# Micro.net
KiCad netlist of a schematic drawn in Altium Designer
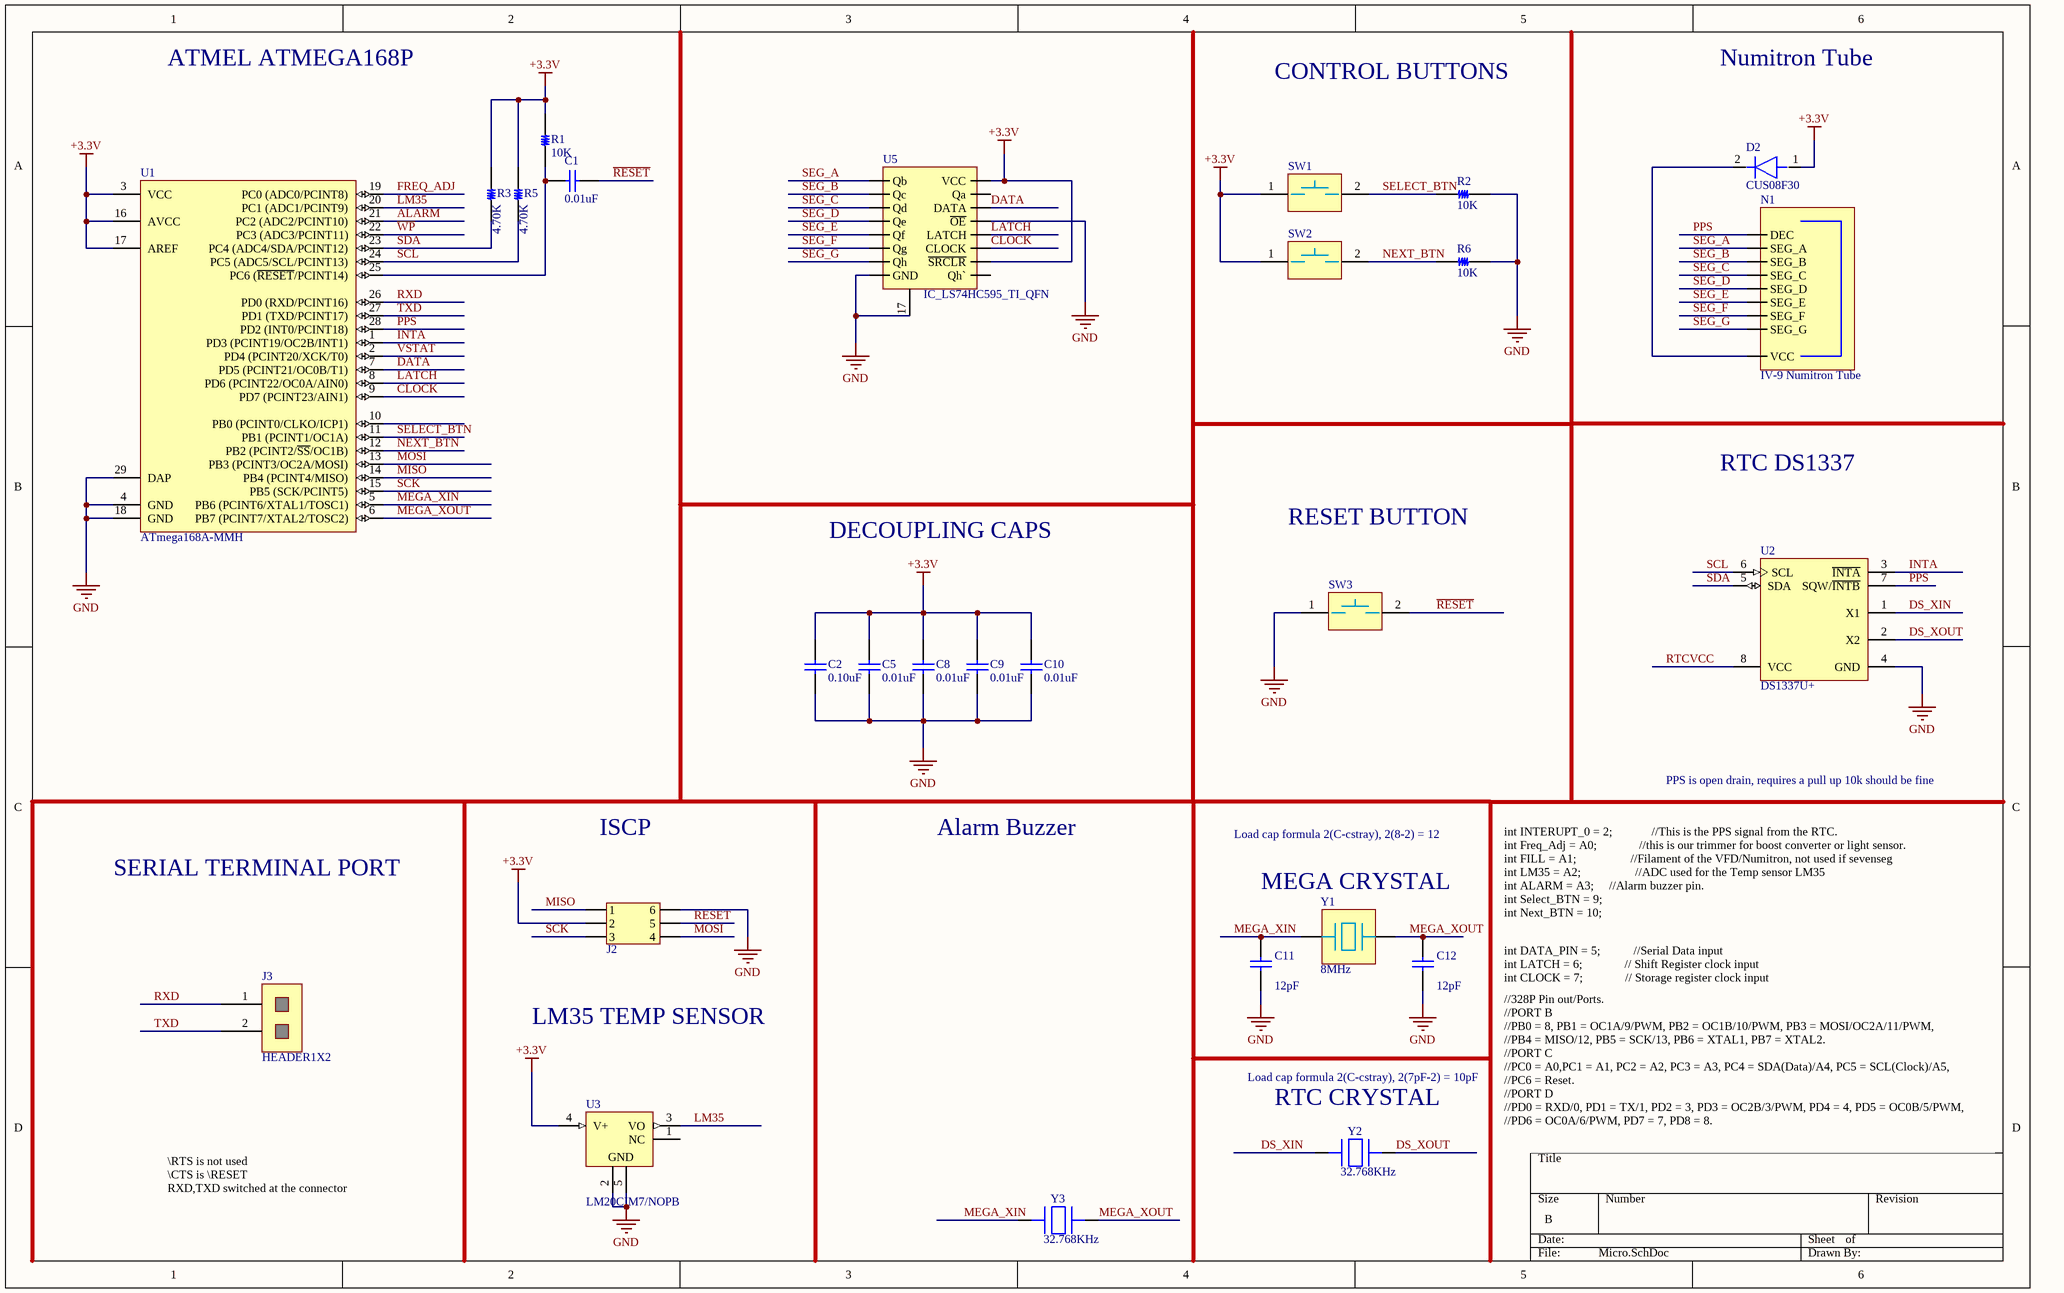
[diagram p0: Micro.SchDoc]

(export (version "E")
  (design (tool "Eeschema 10.0.6"))
  (components
    (comp (ref "C1")
      (value "0.01uF")
      (footprint "DISCRETE:C1608N")
      (description "CAP CER 10000PF 50V 5% X7R 0603")
      (fields (field (name "TOLERANCE") "10%") (field (name "VOLTAGE") "50V"))
      (libsource (lib "DISCRETE_CAP") (part "C103_0603_X7R_50V0_5%_Kemet"))
    )
    (comp (ref "C2")
      (value "0.10uF")
      (footprint "DISCRETE:C1005N")
      (description "CAP CER 0.1UF 16V 10% X7R 0402")
      (fields (field (name "Comment") "C104_0402_X7R_16V0_10%_Kemet"))
      (libsource (lib "DISCRETE_CAP") (part "C104_0402_X7R_16V0_10%_Kemet"))
    )
    (comp (ref "C5")
      (value "0.01uF")
      (footprint "DISCRETE:C1005N")
      (description "CAP CER 10000PF 25V 5% X7R 0402")
      (fields (field (name "TOLERANCE") "5%") (field (name "VOLTAGE") "25V"))
      (libsource (lib "DISCRETE_CAP") (part "C103_0402_X7R_25.0V_5%_Kemet"))
    )
    (comp (ref "C8")
      (value "0.01uF")
      (footprint "DISCRETE:C1005N")
      (description "CAP CER 10000PF 25V 5% X7R 0402")
      (fields (field (name "TOLERANCE") "5%") (field (name "VOLTAGE") "25V"))
      (libsource (lib "DISCRETE_CAP") (part "C103_0402_X7R_25.0V_5%_Kemet"))
    )
    (comp (ref "C9")
      (value "0.01uF")
      (footprint "DISCRETE:C1005N")
      (description "CAP CER 10000PF 25V 5% X7R 0402")
      (fields (field (name "TOLERANCE") "5%") (field (name "VOLTAGE") "25V"))
      (libsource (lib "DISCRETE_CAP") (part "C103_0402_X7R_25.0V_5%_Kemet"))
    )
    (comp (ref "C10")
      (value "0.01uF")
      (footprint "DISCRETE:C1005N")
      (description "CAP CER 10000PF 25V 5% X7R 0402")
      (fields (field (name "TOLERANCE") "5%") (field (name "VOLTAGE") "25V"))
      (libsource (lib "DISCRETE_CAP") (part "C103_0402_X7R_25.0V_5%_Kemet"))
    )
    (comp (ref "C11")
      (value "12pF")
      (footprint "DISCRETE:C1608L")
      (description "CAP CER 12PF 50V 5% C0G 0603")
      (fields (field (name "Comment") "C120-0603-COG-NPO-5%"))
      (libsource (lib "DISCRETE_CAP") (part "C120-0603-C0G-NPO-5%_TDK"))
    )
    (comp (ref "C12")
      (value "12pF")
      (footprint "DISCRETE:C1608L")
      (description "CAP CER 12PF 50V 5% C0G 0603")
      (fields (field (name "Comment") "C120-0603-COG-NPO-5%"))
      (libsource (lib "DISCRETE_CAP") (part "C120-0603-C0G-NPO-5%_TDK"))
    )
    (comp (ref "D2")
      (value "CUS08F30")
      (footprint "DISCRETE:DIODE-USC")
      (description "DIODE SCHOTTKY 30V 800MA USC")
      (libsource (lib "DISCRETE_DIODE") (part "DIODE-CUS08F30-30v-800MA-USC-Toshiba"))
    )
    (comp (ref "J2")
      (value "HEADER 3x2 50mil FCI")
      (footprint "EMACH_CON:3x2 50mil header_FCI")
      (description "CONN HEADER 6POS DL UNSHRD SMD")
      (libsource (lib "EMACH_CON") (part "HEADER 3x2 50mil FCI"))
    )
    (comp (ref "J3")
      (value "HEADER1X2")
      (footprint "EMECH_CONNECTOR:CONN_2P_SINGLE_100MIL")
      (fields (field (name "MANUFACTURER") "MOLEX") (field (name "PART NUMBER") "22-28-4360"))
      (libsource (lib "EMECH_CONNECTOR") (part "CONN_2P_Header"))
    )
    (comp (ref "N1")
      (value "IV-9 Numitron Tube")
      (footprint "TPH:IV-9 Straight Header")
      (libsource (lib "TPH") (part "IV-9 Numitron Tube"))
    )
    (comp (ref "R1")
      (value "10K")
      (footprint "DISCRETE:C1005N")
      (description "RES 10K OHM 1/10W 5% 0402 SMD")
      (fields (field (name "TOLERANCE") "5%"))
      (libsource (lib "DISCRETE_RESISTOR") (part "R103_0402_5%_Panasonic"))
    )
    (comp (ref "R2")
      (value "10K")
      (footprint "DISCRETE:C1005N")
      (description "RES 10K OHM 1/10W 5% 0402 SMD")
      (fields (field (name "TOLERANCE") "5%"))
      (libsource (lib "DISCRETE_RESISTOR") (part "R103_0402_5%_Panasonic"))
    )
    (comp (ref "R3")
      (value "4.70K")
      (footprint "DISCRETE:C1005N")
      (description "RES 4.7K OHM 1/10W 1% 0402 SMD")
      (fields (field (name "TOLERANCE") "1%") (field (name "Comment") "R472-0402-1%"))
      (libsource (lib "DISCRETE_RESISTOR") (part "R472-0402-1%"))
    )
    (comp (ref "R5")
      (value "4.70K")
      (footprint "DISCRETE:C1005N")
      (description "RES 4.7K OHM 1/10W 1% 0402 SMD")
      (fields (field (name "TOLERANCE") "1%") (field (name "Comment") "R472-0402-1%"))
      (libsource (lib "DISCRETE_RESISTOR") (part "R472-0402-1%"))
    )
    (comp (ref "R6")
      (value "10K")
      (footprint "DISCRETE:C1005N")
      (description "RES 10K OHM 1/10W 5% 0402 SMD")
      (fields (field (name "TOLERANCE") "5%"))
      (libsource (lib "DISCRETE_RESISTOR") (part "R103_0402_5%_Panasonic"))
    )
    (comp (ref "SW1")
      (value "SPST-NO_6mm_x_3.5mm")
      (footprint "SWITCH:SPST_NO_6x3.5")
      (description "SWITCH TACTILE SPST-NO 0.05A 24V")
      (libsource (lib "SWITCH") (part "SPST-NO_6mm_x_3.5mm"))
    )
    (comp (ref "SW2")
      (value "SPST-NO_6mm_x_3.5mm")
      (footprint "SWITCH:SPST_NO_6x3.5")
      (description "SWITCH TACTILE SPST-NO 0.05A 24V")
      (libsource (lib "SWITCH") (part "SPST-NO_6mm_x_3.5mm"))
    )
    (comp (ref "SW3")
      (value "SPST-NO_6mm_x_3.5mm")
      (footprint "SWITCH:SPST_NO_6x3.5")
      (description "SWITCH TACTILE SPST-NO 0.05A 24V")
      (libsource (lib "SWITCH") (part "SPST-NO_6mm_x_3.5mm"))
    )
    (comp (ref "U1")
      (value "ATmega168A-MMH")
      (footprint "28M1_N")
      (libsource (lib "Microcontroller megaAVR") (part "ATmega168A-MMH"))
    )
    (comp (ref "U2")
      (value "DS1337U+")
      (footprint "U8+1_N")
      (description "I2C Serial Real-Time Clock, 8-Pin uSOP, -40 to 85 degC, Pb-Free")
      (libsource (lib "Real-Time Clocks (RTCs)") (part "DS1337U+"))
    )
    (comp (ref "U3")
      (value "LM20CIM7/NOPB")
      (footprint "MAA05A_N")
      (description "2.4V, 10µA Temperature Sensor, 5-pin SC-70 Micro SMD, Pb-Free")
      (fields (field (name "MANUFACTURER") "National Semiconductor"))
      (libsource (lib "Temperature Sensor") (part "LM20CIM7/NOPB"))
    )
    (comp (ref "U5")
      (value "IC_LS74HC595_TI_QFN")
      (footprint "IC:QFN50P350X250X100_HS-17N")
      (description "IC 8-BIT SHIFT REGISTER 16-DIP")
      (libsource (lib "TPH") (part "IC_LS74HC595_TI_QFN"))
    )
    (comp (ref "Y1")
      (value "8MHz")
      (footprint "IC:NDK_8MHZ_CRYSTAL")
      (description "Crystal 8.0000MHz 50ppm 8pF 500 Ohm -40°C - 150°C AEC-Q200 Surface Mount 2-SMD")
      (fields (field (name "Comment") "CRYSTAL_8Mhz_8pF_Micro_NDK"))
      (libsource (lib "Crystal") (part "CRYSTAL_8Mhz_8pF_Micro_NDK"))
    )
    (comp (ref "Y2")
      (value "32.768KHz")
      (footprint "EMECH_PIEZO:ABS05")
      (description "Crystal 32.7680kHz 20ppm 12.5pF 90 kOhm -40°C - 85°C Surface Mount 2-SMD")
      (libsource (lib "EMECH_PIEZO") (part "CRYSTAL-32.768KHZ_ABS-Micro"))
    )
    (comp (ref "Y3")
      (value "32.768KHz")
      (footprint "EMECH_PIEZO:ABS05")
      (description "Crystal 32.7680kHz 20ppm 12.5pF 90 kOhm -40°C - 85°C Surface Mount 2-SMD")
      (libsource (lib "EMECH_PIEZO") (part "CRYSTAL-32.768KHZ_ABS-Micro"))
    )
  )
  (nets
    (net (code "1") (name "+3.3V") (class "Default")
      (node (ref "C10") (pin "2") (pinfunction "2_2") (pintype "passive"))
      (node (ref "C2") (pin "2") (pinfunction "2_2") (pintype "passive"))
      (node (ref "C5") (pin "2") (pinfunction "2_2") (pintype "passive"))
      (node (ref "C8") (pin "2") (pinfunction "2_2") (pintype "passive"))
      (node (ref "C9") (pin "2") (pinfunction "2_2") (pintype "passive"))
      (node (ref "D2") (pin "1") (pintype "passive"))
      (node (ref "J2") (pin "2") (pinfunction "2_2") (pintype "passive"))
      (node (ref "R1") (pin "2") (pinfunction "2_2") (pintype "passive"))
      (node (ref "R3") (pin "2") (pinfunction "2_2") (pintype "passive"))
      (node (ref "R5") (pin "2") (pinfunction "2_2") (pintype "passive"))
      (node (ref "SW1") (pin "1") (pinfunction "1_1") (pintype "passive"))
      (node (ref "SW2") (pin "1") (pinfunction "1_1") (pintype "passive"))
      (node (ref "U1") (pin "16") (pinfunction "AVCC_16") (pintype "power_in"))
      (node (ref "U1") (pin "17") (pinfunction "AREF_17") (pintype "power_in"))
      (node (ref "U1") (pin "3") (pinfunction "VCC_3") (pintype "power_in"))
      (node (ref "U3") (pin "4") (pinfunction "V+_4") (pintype "input"))
      (node (ref "U5") (pin "10") (pinfunction "SRCLR_10") (pintype "passive"))
      (node (ref "U5") (pin "16") (pinfunction "VCC_16") (pintype "passive"))
    )
    (net (code "2") (name "/ALARM") (class "Default")
      (node (ref "U1") (pin "21") (pinfunction "PC2_(ADC2/PCINT10)_21") (pintype "bidirectional"))
    )
    (net (code "3") (name "/CLOCK") (class "Default")
      (node (ref "U1") (pin "9") (pinfunction "PD7_(PCINT23/AIN1)_9") (pintype "bidirectional"))
      (node (ref "U5") (pin "11") (pinfunction "CLOCK_11") (pintype "passive"))
    )
    (net (code "4") (name "/DATA") (class "Default")
      (node (ref "U1") (pin "7") (pinfunction "PD5_(PCINT21/OC0B/T1)_7") (pintype "bidirectional"))
      (node (ref "U5") (pin "14") (pinfunction "DATA_14") (pintype "passive"))
    )
    (net (code "5") (name "/DS_XIN") (class "Default")
      (node (ref "U2") (pin "1") (pinfunction "X1_1") (pintype "passive"))
      (node (ref "Y2") (pin "2") (pintype "passive"))
    )
    (net (code "6") (name "/DS_XOUT") (class "Default")
      (node (ref "U2") (pin "2") (pinfunction "X2_2") (pintype "passive"))
      (node (ref "Y2") (pin "1") (pintype "passive"))
    )
    (net (code "7") (name "/FREQ_ADJ") (class "Default")
      (node (ref "U1") (pin "19") (pinfunction "PC0_(ADC0/PCINT8)_19") (pintype "bidirectional"))
    )
    (net (code "8") (name "/INTA") (class "Default")
      (node (ref "U1") (pin "1") (pinfunction "PD3_(PCINT19/OC2B/INT1)_1") (pintype "bidirectional"))
      (node (ref "U2") (pin "3") (pinfunction "~{INTA}_3") (pintype "open_collector"))
    )
    (net (code "9") (name "/LATCH") (class "Default")
      (node (ref "U1") (pin "8") (pinfunction "PD6_(PCINT22/OC0A/AIN0)_8") (pintype "bidirectional"))
      (node (ref "U5") (pin "12") (pinfunction "LATCH_12") (pintype "passive"))
    )
    (net (code "10") (name "/LM35") (class "Default")
      (node (ref "U1") (pin "20") (pinfunction "PC1_(ADC1/PCINT9)_20") (pintype "bidirectional"))
      (node (ref "U3") (pin "3") (pinfunction "VO_3") (pintype "output"))
    )
    (net (code "11") (name "/MEGA_XIN") (class "Default")
      (node (ref "C11") (pin "2") (pinfunction "2_2") (pintype "passive"))
      (node (ref "U1") (pin "5") (pinfunction "PB6_(PCINT6/XTAL1/TOSC1)_5") (pintype "bidirectional"))
      (node (ref "Y1") (pin "1") (pinfunction "1_1") (pintype "passive"))
      (node (ref "Y3") (pin "2") (pintype "passive"))
    )
    (net (code "12") (name "/MEGA_XOUT") (class "Default")
      (node (ref "C12") (pin "2") (pinfunction "2_2") (pintype "passive"))
      (node (ref "U1") (pin "6") (pinfunction "PB7_(PCINT7/XTAL2/TOSC2)_6") (pintype "bidirectional"))
      (node (ref "Y1") (pin "2") (pinfunction "2_2") (pintype "passive"))
      (node (ref "Y3") (pin "1") (pintype "passive"))
    )
    (net (code "13") (name "/MISO") (class "Default")
      (node (ref "J2") (pin "1") (pinfunction "1_1") (pintype "passive"))
      (node (ref "U1") (pin "14") (pinfunction "PB4_(PCINT4/MISO)_14") (pintype "bidirectional"))
    )
    (net (code "14") (name "/MOSI") (class "Default")
      (node (ref "J2") (pin "4") (pinfunction "4_4") (pintype "passive"))
      (node (ref "U1") (pin "13") (pinfunction "PB3_(PCINT3/OC2A/MOSI)_13") (pintype "bidirectional"))
    )
    (net (code "15") (name "/NEXT_BTN") (class "Default")
      (node (ref "R6") (pin "2") (pinfunction "2_2") (pintype "passive"))
      (node (ref "SW2") (pin "2") (pinfunction "2_2") (pintype "passive"))
      (node (ref "U1") (pin "12") (pinfunction "PB2_(PCINT2/~{SS}/OC1B)_12") (pintype "bidirectional"))
    )
    (net (code "16") (name "/PPS") (class "Default")
      (node (ref "N1") (pin "2") (pinfunction "DEC_2") (pintype "passive"))
      (node (ref "U1") (pin "28") (pinfunction "PD2_(INT0/PCINT18)_28") (pintype "bidirectional"))
      (node (ref "U2") (pin "7") (pinfunction "SQW/~{INTB}_7") (pintype "open_collector"))
    )
    (net (code "17") (name "/RESET") (class "Default")
      (node (ref "C1") (pin "1") (pinfunction "1_1") (pintype "passive"))
      (node (ref "J2") (pin "5") (pinfunction "5_5") (pintype "passive"))
      (node (ref "SW3") (pin "2") (pinfunction "2_2") (pintype "passive"))
    )
    (net (code "18") (name "/RTCVCC") (class "Default")
      (node (ref "U2") (pin "8") (pinfunction "VCC_8") (pintype "power_in"))
    )
    (net (code "19") (name "/RXD") (class "Default")
      (node (ref "J3") (pin "1") (pinfunction "1_1") (pintype "passive"))
      (node (ref "U1") (pin "26") (pinfunction "PD0_(RXD/PCINT16)_26") (pintype "bidirectional"))
    )
    (net (code "20") (name "/SCK") (class "Default")
      (node (ref "J2") (pin "3") (pinfunction "3_3") (pintype "passive"))
      (node (ref "U1") (pin "15") (pinfunction "PB5_(SCK/PCINT5)_15") (pintype "bidirectional"))
    )
    (net (code "21") (name "/SCL") (class "Default")
      (node (ref "R5") (pin "1") (pinfunction "1_1") (pintype "passive"))
      (node (ref "U1") (pin "24") (pinfunction "PC5_(ADC5/SCL/PCINT13)_24") (pintype "bidirectional"))
      (node (ref "U2") (pin "6") (pinfunction "SCL_6") (pintype "input"))
    )
    (net (code "22") (name "/SDA") (class "Default")
      (node (ref "R3") (pin "1") (pinfunction "1_1") (pintype "passive"))
      (node (ref "U1") (pin "23") (pinfunction "PC4_(ADC4/SDA/PCINT12)_23") (pintype "bidirectional"))
      (node (ref "U2") (pin "5") (pinfunction "SDA_5") (pintype "bidirectional"))
    )
    (net (code "23") (name "/SEG_A") (class "Default")
      (node (ref "N1") (pin "5") (pinfunction "SEG_A_5") (pintype "passive"))
      (node (ref "U5") (pin "1") (pinfunction "Qb_1") (pintype "passive"))
    )
    (net (code "24") (name "/SEG_B") (class "Default")
      (node (ref "N1") (pin "3") (pinfunction "SEG_B_3") (pintype "passive"))
      (node (ref "U5") (pin "2") (pinfunction "Qc_2") (pintype "passive"))
    )
    (net (code "25") (name "/SEG_C") (class "Default")
      (node (ref "N1") (pin "4") (pinfunction "SEG_C_4") (pintype "passive"))
      (node (ref "U5") (pin "3") (pinfunction "Qd_3") (pintype "passive"))
    )
    (net (code "26") (name "/SEG_D") (class "Default")
      (node (ref "N1") (pin "8") (pinfunction "SEG_D_8") (pintype "passive"))
      (node (ref "U5") (pin "4") (pinfunction "Qe_4") (pintype "passive"))
    )
    (net (code "27") (name "/SEG_E") (class "Default")
      (node (ref "N1") (pin "9") (pinfunction "SEG_E_9") (pintype "passive"))
      (node (ref "U5") (pin "5") (pinfunction "Qf_5") (pintype "passive"))
    )
    (net (code "28") (name "/SEG_F") (class "Default")
      (node (ref "N1") (pin "6") (pinfunction "SEG_F_6") (pintype "passive"))
      (node (ref "U5") (pin "6") (pinfunction "Qg_6") (pintype "passive"))
    )
    (net (code "29") (name "/SEG_G") (class "Default")
      (node (ref "N1") (pin "7") (pinfunction "SEG_G_7") (pintype "passive"))
      (node (ref "U5") (pin "7") (pinfunction "Qh_7") (pintype "passive"))
    )
    (net (code "30") (name "/SELECT_BTN") (class "Default")
      (node (ref "R2") (pin "2") (pinfunction "2_2") (pintype "passive"))
      (node (ref "SW1") (pin "2") (pinfunction "2_2") (pintype "passive"))
      (node (ref "U1") (pin "11") (pinfunction "PB1_(PCINT1/OC1A)_11") (pintype "bidirectional"))
    )
    (net (code "31") (name "/TXD") (class "Default")
      (node (ref "J3") (pin "2") (pinfunction "2_2") (pintype "passive"))
      (node (ref "U1") (pin "27") (pinfunction "PD1_(TXD/PCINT17)_27") (pintype "bidirectional"))
    )
    (net (code "32") (name "/VSTAT") (class "Default")
      (node (ref "U1") (pin "2") (pinfunction "PD4_(PCINT20/XCK/T0)_2") (pintype "bidirectional"))
    )
    (net (code "33") (name "/WP") (class "Default")
      (node (ref "U1") (pin "22") (pinfunction "PC3_(ADC3/PCINT11)_22") (pintype "bidirectional"))
    )
    (net (code "34") (name "GND") (class "Default")
      (node (ref "C10") (pin "1") (pinfunction "1_1") (pintype "passive"))
      (node (ref "C11") (pin "1") (pinfunction "1_1") (pintype "passive"))
      (node (ref "C12") (pin "1") (pinfunction "1_1") (pintype "passive"))
      (node (ref "C2") (pin "1") (pinfunction "1_1") (pintype "passive"))
      (node (ref "C5") (pin "1") (pinfunction "1_1") (pintype "passive"))
      (node (ref "C8") (pin "1") (pinfunction "1_1") (pintype "passive"))
      (node (ref "C9") (pin "1") (pinfunction "1_1") (pintype "passive"))
      (node (ref "J2") (pin "6") (pinfunction "6_6") (pintype "passive"))
      (node (ref "R2") (pin "1") (pinfunction "1_1") (pintype "passive"))
      (node (ref "R6") (pin "1") (pinfunction "1_1") (pintype "passive"))
      (node (ref "SW3") (pin "1") (pinfunction "1_1") (pintype "passive"))
      (node (ref "U1") (pin "18") (pinfunction "GND_18") (pintype "power_in"))
      (node (ref "U1") (pin "29") (pinfunction "DAP_29") (pintype "power_in"))
      (node (ref "U1") (pin "4") (pinfunction "GND_4") (pintype "power_in"))
      (node (ref "U2") (pin "4") (pinfunction "GND_4") (pintype "power_in"))
      (node (ref "U3") (pin "2") (pinfunction "GND_2") (pintype "power_in"))
      (node (ref "U3") (pin "5") (pinfunction "GND_5") (pintype "power_in"))
      (node (ref "U5") (pin "13") (pinfunction "OE_13") (pintype "passive"))
      (node (ref "U5") (pin "17") (pinfunction "17_17") (pintype "passive"))
      (node (ref "U5") (pin "8") (pinfunction "GND_8") (pintype "passive"))
    )
    (net (code "35") (name "Net-(N1-VCC)") (class "Default")
      (node (ref "D2") (pin "2") (pintype "passive"))
      (node (ref "N1") (pin "1") (pinfunction "VCC_1") (pintype "passive"))
    )
    (net (code "36") (name "Net-(U1-PC6_(~{RESET}{slash}PCINT14))") (class "Default")
      (node (ref "C1") (pin "2") (pinfunction "2_2") (pintype "passive"))
      (node (ref "R1") (pin "1") (pinfunction "1_1") (pintype "passive"))
      (node (ref "U1") (pin "25") (pinfunction "PC6_(~{RESET}/PCINT14)_25") (pintype "bidirectional"))
    )
    (net (code "37") (name "unconnected-(U1-PB0_(PCINT0{slash}CLKO{slash}ICP1)-Pad10)") (class "Default")
      (node (ref "U1") (pin "10") (pinfunction "PB0_(PCINT0/CLKO/ICP1)_10") (pintype "bidirectional"))
    )
    (net (code "38") (name "unconnected-(U3-NC-Pad1)") (class "Default")
      (node (ref "U3") (pin "1") (pinfunction "NC_1") (pintype "passive"))
    )
    (net (code "39") (name "unconnected-(U5-Qa-Pad15)") (class "Default")
      (node (ref "U5") (pin "15") (pinfunction "Qa_15") (pintype "passive"))
    )
    (net (code "40") (name "unconnected-(U5-Qh`-Pad9)") (class "Default")
      (node (ref "U5") (pin "9") (pinfunction "Qh`_9") (pintype "passive"))
    )
  )
)
